# SisMin.net
KiCad netlist of a schematic drawn in EAGLE
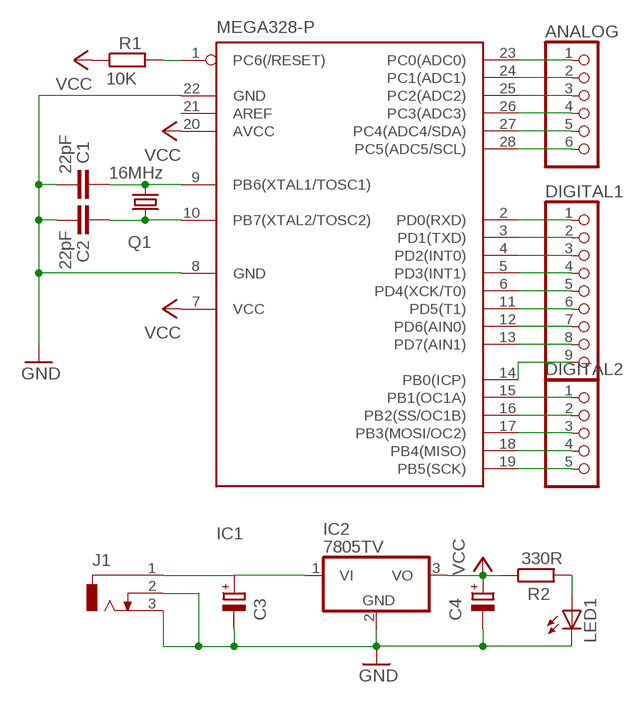
[diagram p0: schematic, sheet 1]

(export (version "E")
  (design (tool "Eeschema 10.0.6"))
  (components
    (comp (ref "ANALOG")
      (value "PINHD-1X6")
      (footprint "eagle-import:1X06")
      (libsource (lib "eagle-import") (part "PINHD-1X6"))
    )
    (comp (ref "C1")
      (value "22pF")
      (footprint "eagle-import:C025-024X044")
      (libsource (lib "eagle-import") (part "C-EU025-024X044"))
    )
    (comp (ref "C2")
      (value "22pF")
      (footprint "eagle-import:C025-024X044")
      (libsource (lib "eagle-import") (part "C-EU025-024X044"))
    )
    (comp (ref "C3")
      (value "CPOL-EUE2.5-6")
      (footprint "eagle-import:E2,5-6")
      (libsource (lib "eagle-import") (part "CPOL-EUE2.5-6"))
    )
    (comp (ref "C4")
      (value "CPOL-EUE2.5-6")
      (footprint "eagle-import:E2,5-6")
      (libsource (lib "eagle-import") (part "CPOL-EUE2.5-6"))
    )
    (comp (ref "DIGITAL1")
      (value "PINHD-1X9")
      (footprint "eagle-import:1X09")
      (libsource (lib "eagle-import") (part "PINHD-1X9"))
    )
    (comp (ref "DIGITAL2")
      (value "PINHD-1X5")
      (footprint "eagle-import:1X05")
      (libsource (lib "eagle-import") (part "PINHD-1X5"))
    )
    (comp (ref "IC1")
      (value "MEGA328-P")
      (footprint "eagle-import:DIL28-3")
      (libsource (lib "eagle-import") (part "MEGA8-P"))
    )
    (comp (ref "IC2")
      (value "7805TV")
      (footprint "eagle-import:TO220V")
      (libsource (lib "eagle-import") (part "78TV05"))
    )
    (comp (ref "J1")
      (value "DCJ0303")
      (footprint "eagle-import:DCJ0303")
      (libsource (lib "eagle-import") (part "DCJ0303"))
    )
    (comp (ref "LED1")
      (value "LED3MM")
      (footprint "eagle-import:LED3MM")
      (libsource (lib "eagle-import") (part "LED3MM"))
    )
    (comp (ref "Q1")
      (value "16MHz")
      (footprint "eagle-import:HC49U70")
      (libsource (lib "eagle-import") (part "CRYSTALHC49U70"))
    )
    (comp (ref "R1")
      (value "10K")
      (footprint "eagle-import:0207_10")
      (libsource (lib "eagle-import") (part "R-EU_0207/10"))
    )
    (comp (ref "R2")
      (value "330R")
      (footprint "eagle-import:0207_10")
      (libsource (lib "eagle-import") (part "R-EU_0207/10"))
    )
  )
  (nets
    (net (code "1") (name "GND") (class "Default")
      (node (ref "C1") (pin "2") (pinfunction "2_2") (pintype "passive"))
      (node (ref "C2") (pin "2") (pinfunction "2_2") (pintype "passive"))
      (node (ref "C3") (pin "-") (pinfunction "-_-") (pintype "passive"))
      (node (ref "C4") (pin "-") (pinfunction "-_-") (pintype "passive"))
      (node (ref "IC1") (pin "22") (pinfunction "GND_22") (pintype "power_in"))
      (node (ref "IC1") (pin "8") (pinfunction "GND_8") (pintype "power_in"))
      (node (ref "IC2") (pin "2") (pinfunction "GND_2") (pintype "passive"))
      (node (ref "J1") (pin "2") (pinfunction "2_2") (pintype "passive"))
      (node (ref "J1") (pin "3") (pinfunction "3_3") (pintype "passive"))
      (node (ref "LED1") (pin "K") (pinfunction "C_K") (pintype "passive"))
    )
    (net (code "2") (name "Net-(IC1-PB0(ICP))") (class "Default")
      (node (ref "DIGITAL1") (pin "9") (pinfunction "9_9") (pintype "passive"))
      (node (ref "IC1") (pin "14") (pinfunction "PB0(ICP)_14") (pintype "bidirectional"))
    )
    (net (code "3") (name "Net-(IC1-PB1(OC1A))") (class "Default")
      (node (ref "DIGITAL2") (pin "1") (pinfunction "1_1") (pintype "passive"))
      (node (ref "IC1") (pin "15") (pinfunction "PB1(OC1A)_15") (pintype "bidirectional"))
    )
    (net (code "4") (name "Net-(IC1-PB2(SS{slash}OC1B))") (class "Default")
      (node (ref "DIGITAL2") (pin "2") (pinfunction "2_2") (pintype "passive"))
      (node (ref "IC1") (pin "16") (pinfunction "PB2(SS/OC1B)_16") (pintype "bidirectional"))
    )
    (net (code "5") (name "Net-(IC1-PB3(MOSI{slash}OC2))") (class "Default")
      (node (ref "DIGITAL2") (pin "3") (pinfunction "3_3") (pintype "passive"))
      (node (ref "IC1") (pin "17") (pinfunction "PB3(MOSI/OC2)_17") (pintype "bidirectional"))
    )
    (net (code "6") (name "Net-(IC1-PB4(MISO))") (class "Default")
      (node (ref "DIGITAL2") (pin "4") (pinfunction "4_4") (pintype "passive"))
      (node (ref "IC1") (pin "18") (pinfunction "PB4(MISO)_18") (pintype "bidirectional"))
    )
    (net (code "7") (name "Net-(IC1-PB5(SCK))") (class "Default")
      (node (ref "DIGITAL2") (pin "5") (pinfunction "5_5") (pintype "passive"))
      (node (ref "IC1") (pin "19") (pinfunction "PB5(SCK)_19") (pintype "bidirectional"))
    )
    (net (code "8") (name "Net-(IC1-PB6(XTAL1{slash}TOSC1))") (class "Default")
      (node (ref "C1") (pin "1") (pinfunction "1_1") (pintype "passive"))
      (node (ref "IC1") (pin "9") (pinfunction "PB6(XTAL1/TOSC1)_9") (pintype "bidirectional"))
      (node (ref "Q1") (pin "1") (pinfunction "1_1") (pintype "passive"))
    )
    (net (code "9") (name "Net-(IC1-PB7(XTAL2{slash}TOSC2))") (class "Default")
      (node (ref "C2") (pin "1") (pinfunction "1_1") (pintype "passive"))
      (node (ref "IC1") (pin "10") (pinfunction "PB7(XTAL2/TOSC2)_10") (pintype "bidirectional"))
      (node (ref "Q1") (pin "2") (pinfunction "2_2") (pintype "passive"))
    )
    (net (code "10") (name "Net-(IC1-PC0(ADC0))") (class "Default")
      (node (ref "ANALOG") (pin "1") (pinfunction "1_1") (pintype "passive"))
      (node (ref "IC1") (pin "23") (pinfunction "PC0(ADC0)_23") (pintype "bidirectional"))
    )
    (net (code "11") (name "Net-(IC1-PC1(ADC1))") (class "Default")
      (node (ref "ANALOG") (pin "2") (pinfunction "2_2") (pintype "passive"))
      (node (ref "IC1") (pin "24") (pinfunction "PC1(ADC1)_24") (pintype "bidirectional"))
    )
    (net (code "12") (name "Net-(IC1-PC2(ADC2))") (class "Default")
      (node (ref "ANALOG") (pin "3") (pinfunction "3_3") (pintype "passive"))
      (node (ref "IC1") (pin "25") (pinfunction "PC2(ADC2)_25") (pintype "bidirectional"))
    )
    (net (code "13") (name "Net-(IC1-PC3(ADC3))") (class "Default")
      (node (ref "ANALOG") (pin "4") (pinfunction "4_4") (pintype "passive"))
      (node (ref "IC1") (pin "26") (pinfunction "PC3(ADC3)_26") (pintype "bidirectional"))
    )
    (net (code "14") (name "Net-(IC1-PC4(ADC4{slash}SDA))") (class "Default")
      (node (ref "ANALOG") (pin "5") (pinfunction "5_5") (pintype "passive"))
      (node (ref "IC1") (pin "27") (pinfunction "PC4(ADC4/SDA)_27") (pintype "bidirectional"))
    )
    (net (code "15") (name "Net-(IC1-PC5(ADC5{slash}SCL))") (class "Default")
      (node (ref "ANALOG") (pin "6") (pinfunction "6_6") (pintype "passive"))
      (node (ref "IC1") (pin "28") (pinfunction "PC5(ADC5/SCL)_28") (pintype "bidirectional"))
    )
    (net (code "16") (name "Net-(IC1-PC6({slash}RESET))") (class "Default")
      (node (ref "IC1") (pin "1") (pinfunction "PC6(/RESET)_1") (pintype "bidirectional"))
      (node (ref "R1") (pin "2") (pinfunction "2_2") (pintype "passive"))
    )
    (net (code "17") (name "Net-(IC1-PD0(RXD))") (class "Default")
      (node (ref "DIGITAL1") (pin "1") (pinfunction "1_1") (pintype "passive"))
      (node (ref "IC1") (pin "2") (pinfunction "PD0(RXD)_2") (pintype "bidirectional"))
    )
    (net (code "18") (name "Net-(IC1-PD1(TXD))") (class "Default")
      (node (ref "DIGITAL1") (pin "2") (pinfunction "2_2") (pintype "passive"))
      (node (ref "IC1") (pin "3") (pinfunction "PD1(TXD)_3") (pintype "bidirectional"))
    )
    (net (code "19") (name "Net-(IC1-PD2(INT0))") (class "Default")
      (node (ref "DIGITAL1") (pin "3") (pinfunction "3_3") (pintype "passive"))
      (node (ref "IC1") (pin "4") (pinfunction "PD2(INT0)_4") (pintype "bidirectional"))
    )
    (net (code "20") (name "Net-(IC1-PD3(INT1))") (class "Default")
      (node (ref "DIGITAL1") (pin "4") (pinfunction "4_4") (pintype "passive"))
      (node (ref "IC1") (pin "5") (pinfunction "PD3(INT1)_5") (pintype "bidirectional"))
    )
    (net (code "21") (name "Net-(IC1-PD4(XCK{slash}T0))") (class "Default")
      (node (ref "DIGITAL1") (pin "5") (pinfunction "5_5") (pintype "passive"))
      (node (ref "IC1") (pin "6") (pinfunction "PD4(XCK/T0)_6") (pintype "bidirectional"))
    )
    (net (code "22") (name "Net-(IC1-PD5(T1))") (class "Default")
      (node (ref "DIGITAL1") (pin "6") (pinfunction "6_6") (pintype "passive"))
      (node (ref "IC1") (pin "11") (pinfunction "PD5(T1)_11") (pintype "bidirectional"))
    )
    (net (code "23") (name "Net-(IC1-PD6(AIN0))") (class "Default")
      (node (ref "DIGITAL1") (pin "7") (pinfunction "7_7") (pintype "passive"))
      (node (ref "IC1") (pin "12") (pinfunction "PD6(AIN0)_12") (pintype "bidirectional"))
    )
    (net (code "24") (name "Net-(IC1-PD7(AIN1))") (class "Default")
      (node (ref "DIGITAL1") (pin "8") (pinfunction "8_8") (pintype "passive"))
      (node (ref "IC1") (pin "13") (pinfunction "PD7(AIN1)_13") (pintype "bidirectional"))
    )
    (net (code "25") (name "Net-(IC2-VI)") (class "Default")
      (node (ref "C3") (pin "+") (pinfunction "+_+") (pintype "passive"))
      (node (ref "IC2") (pin "1") (pinfunction "VI_1") (pintype "input"))
      (node (ref "J1") (pin "1") (pinfunction "1_1") (pintype "passive"))
    )
    (net (code "26") (name "Net-(LED1-PadA)") (class "Default")
      (node (ref "LED1") (pin "A") (pinfunction "A_A") (pintype "passive"))
      (node (ref "R2") (pin "2") (pinfunction "2_2") (pintype "passive"))
    )
    (net (code "27") (name "VCC") (class "Default")
      (node (ref "C4") (pin "+") (pinfunction "+_+") (pintype "passive"))
      (node (ref "IC1") (pin "20") (pinfunction "AVCC_20") (pintype "power_in"))
      (node (ref "IC1") (pin "7") (pinfunction "VCC_7") (pintype "power_in"))
      (node (ref "IC2") (pin "3") (pinfunction "VO_3") (pintype "passive"))
      (node (ref "R1") (pin "1") (pinfunction "1_1") (pintype "passive"))
      (node (ref "R2") (pin "1") (pinfunction "1_1") (pintype "passive"))
    )
    (net (code "28") (name "unconnected-(IC1-AREF-Pad21)") (class "Default")
      (node (ref "IC1") (pin "21") (pinfunction "AREF_21") (pintype "passive"))
    )
  )
)
